# Elaborato_2021-05-28.net
KiCad netlist of a schematic drawn in EasyEDA
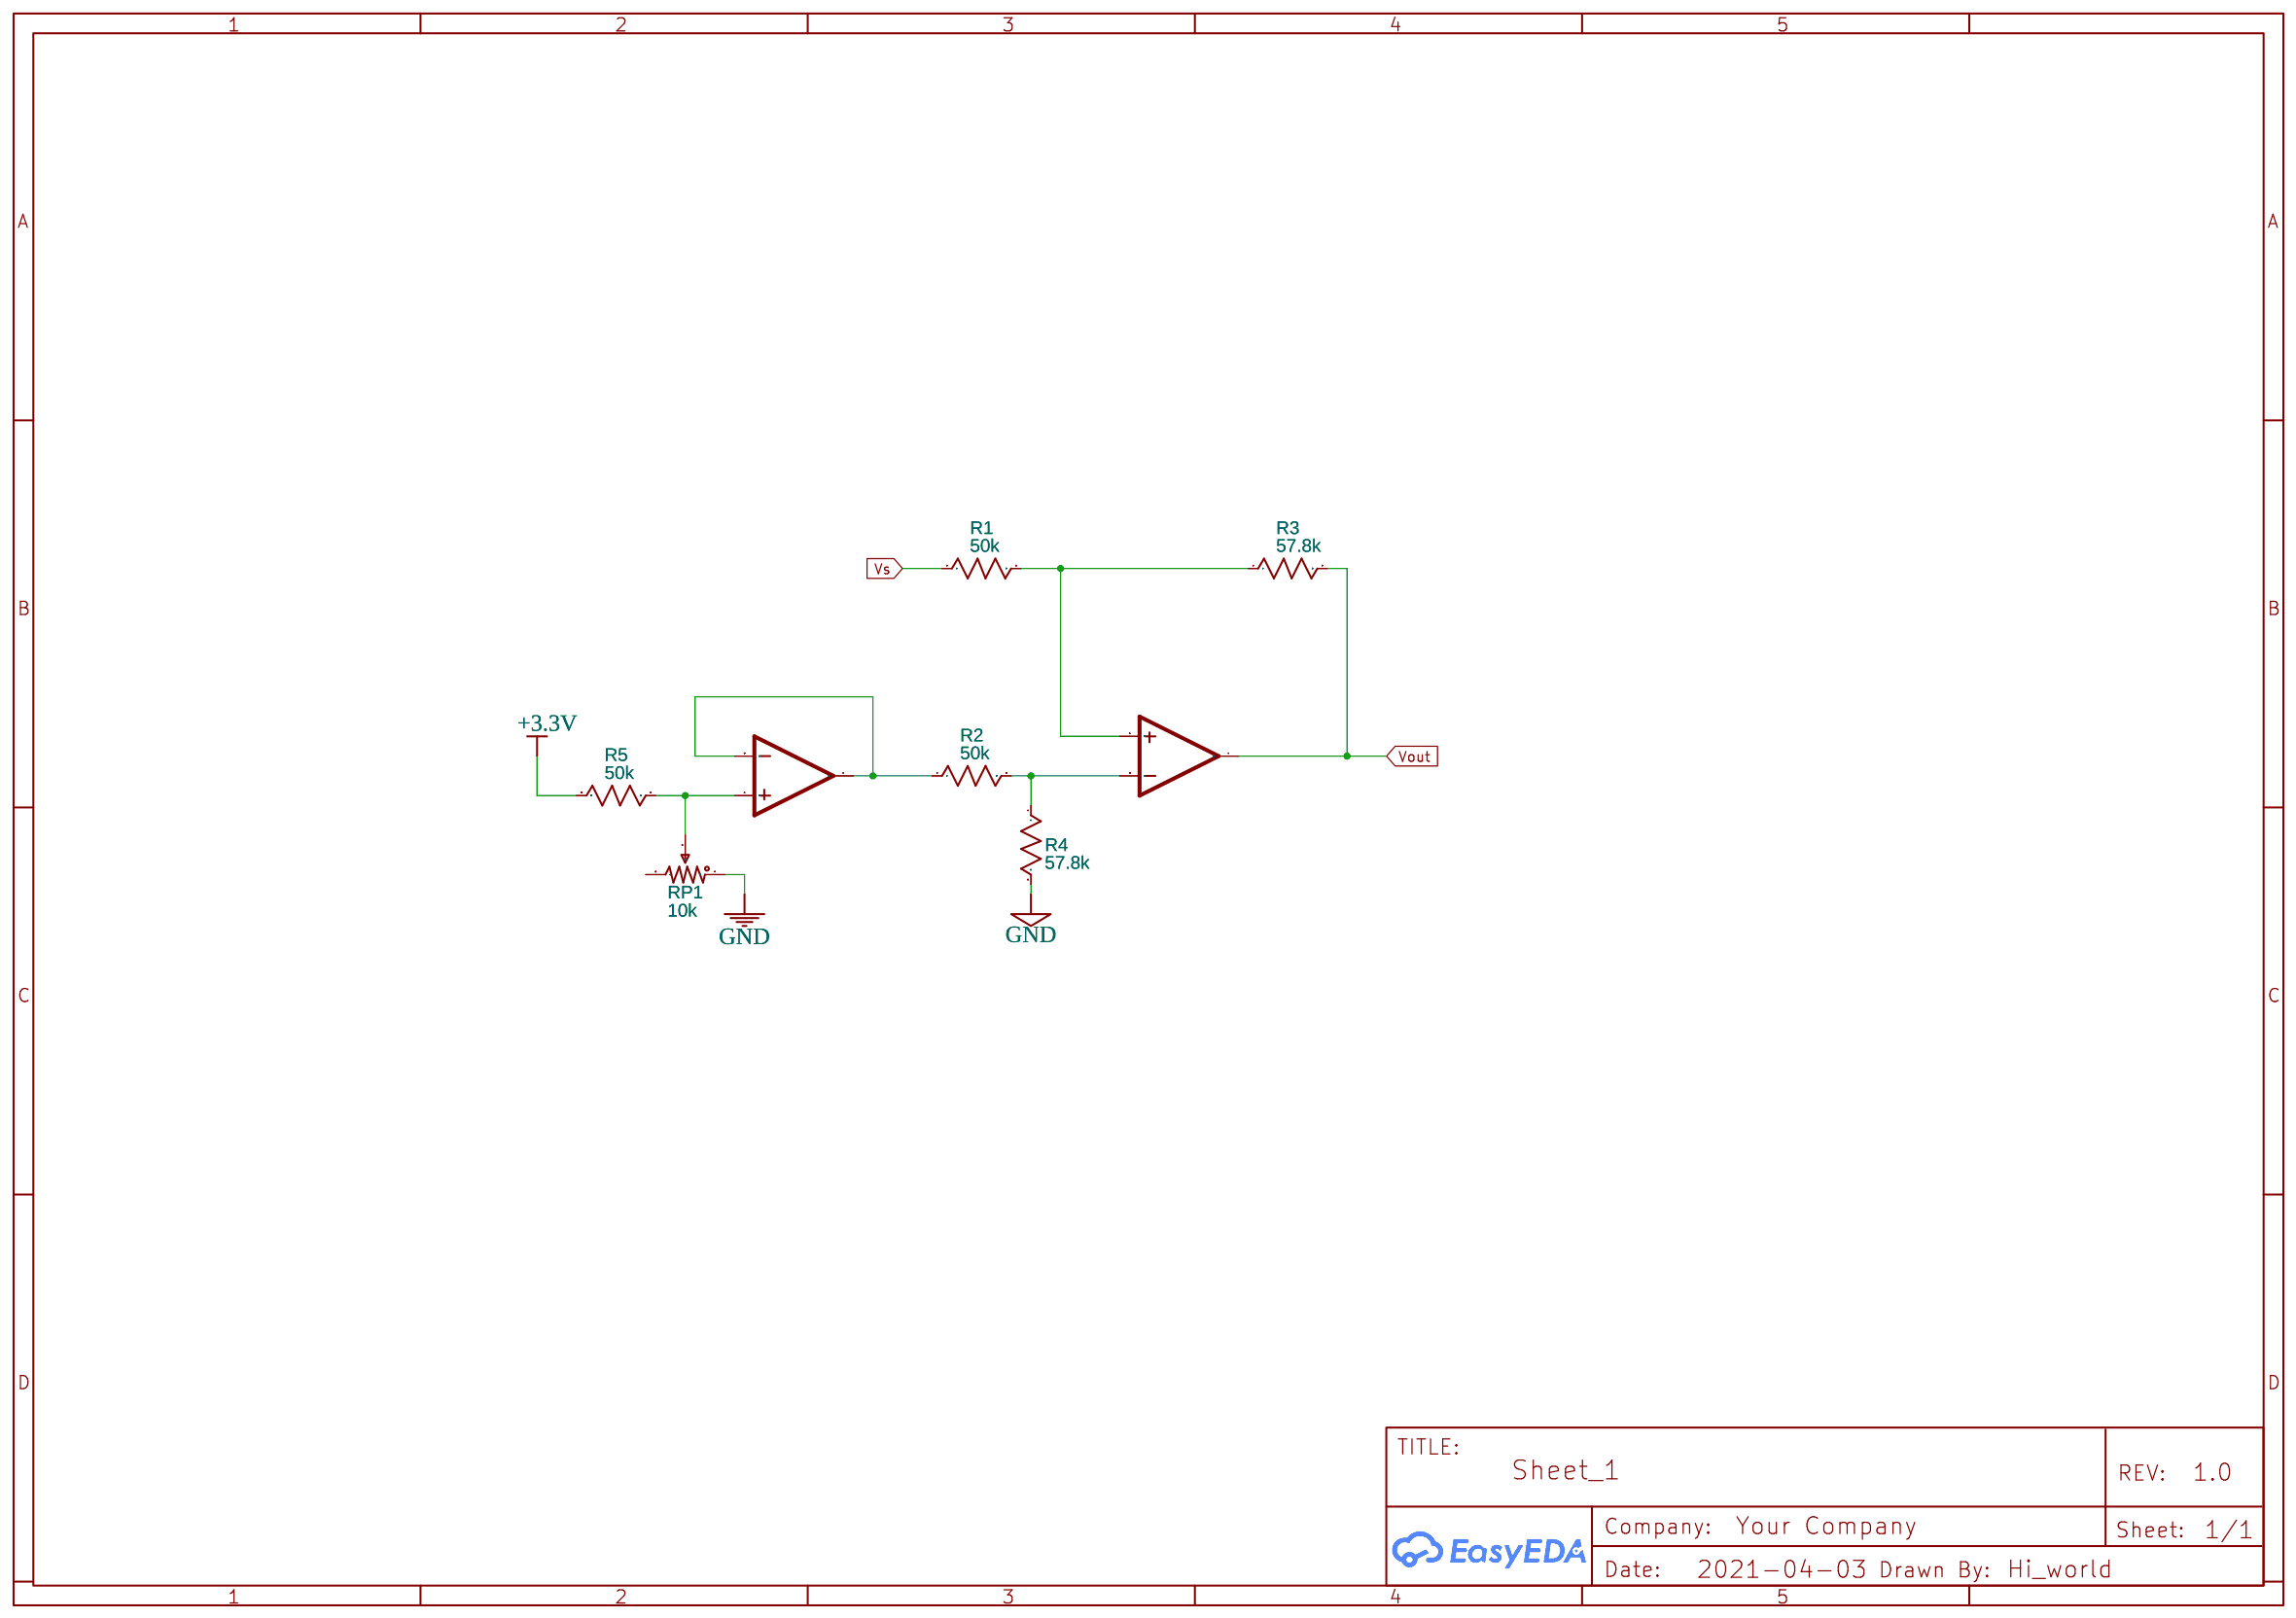
[diagram p0: Differenziale_condizionamento]
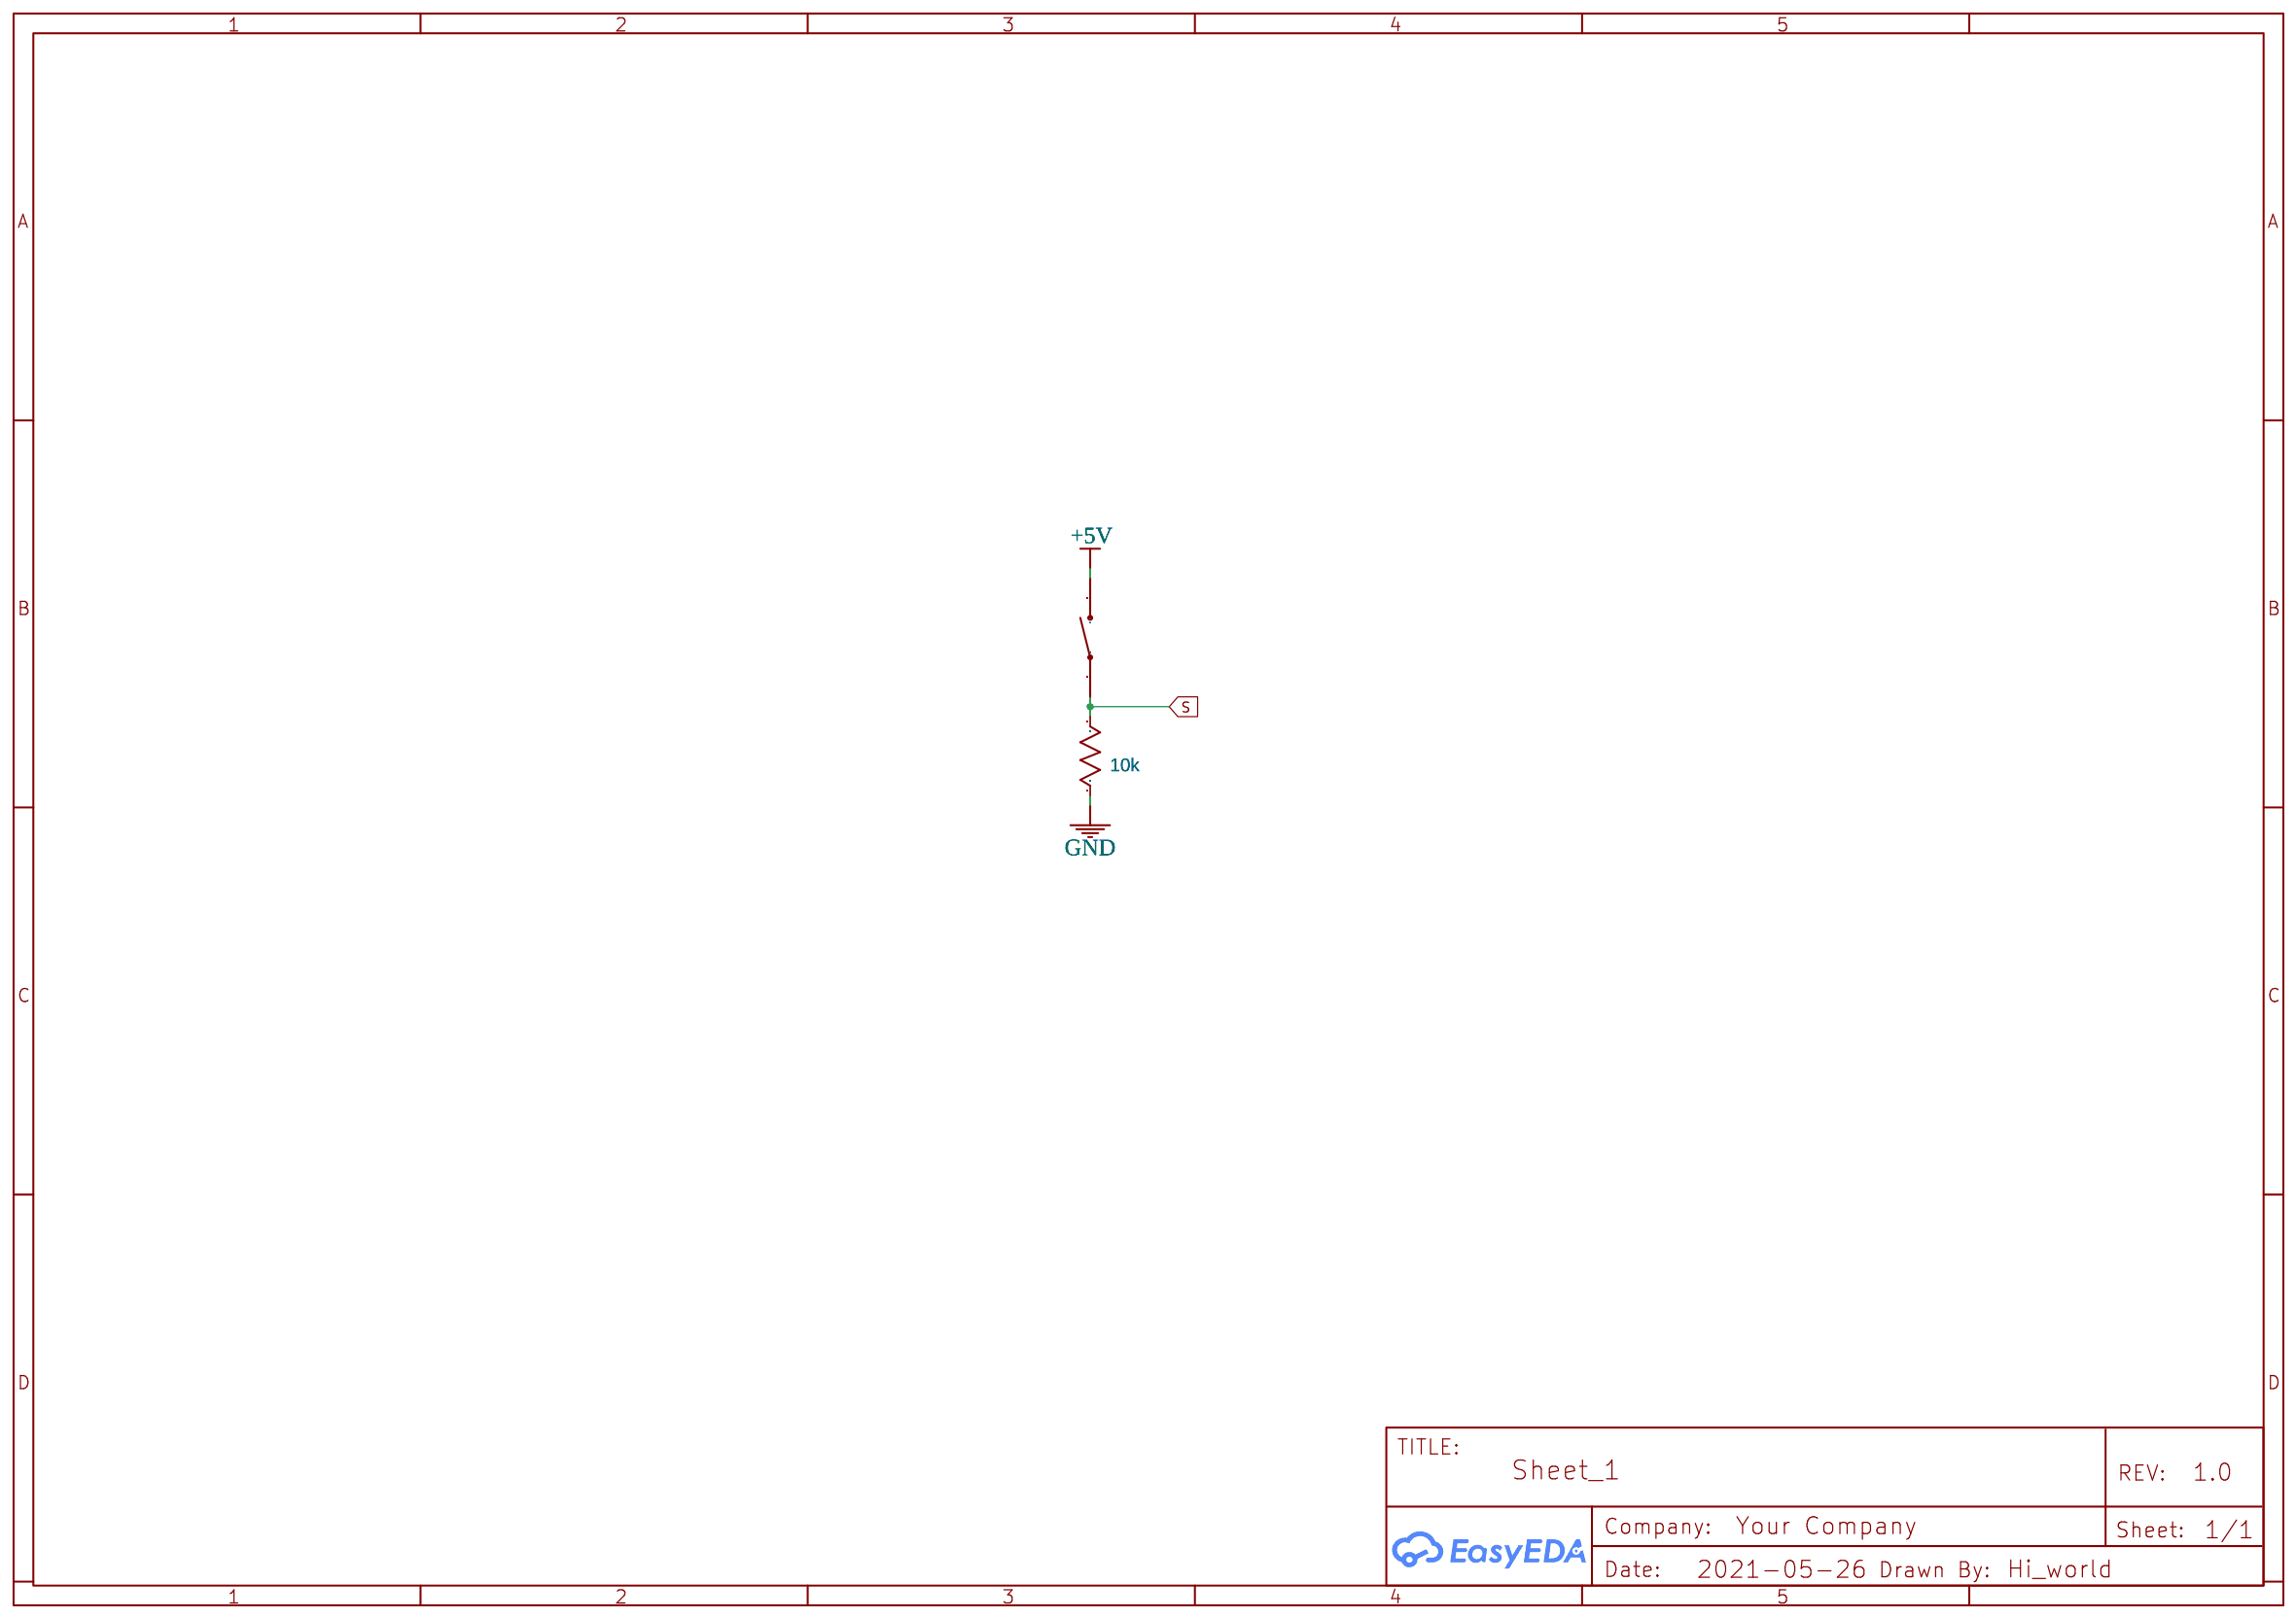
[diagram p1: Pull_down]
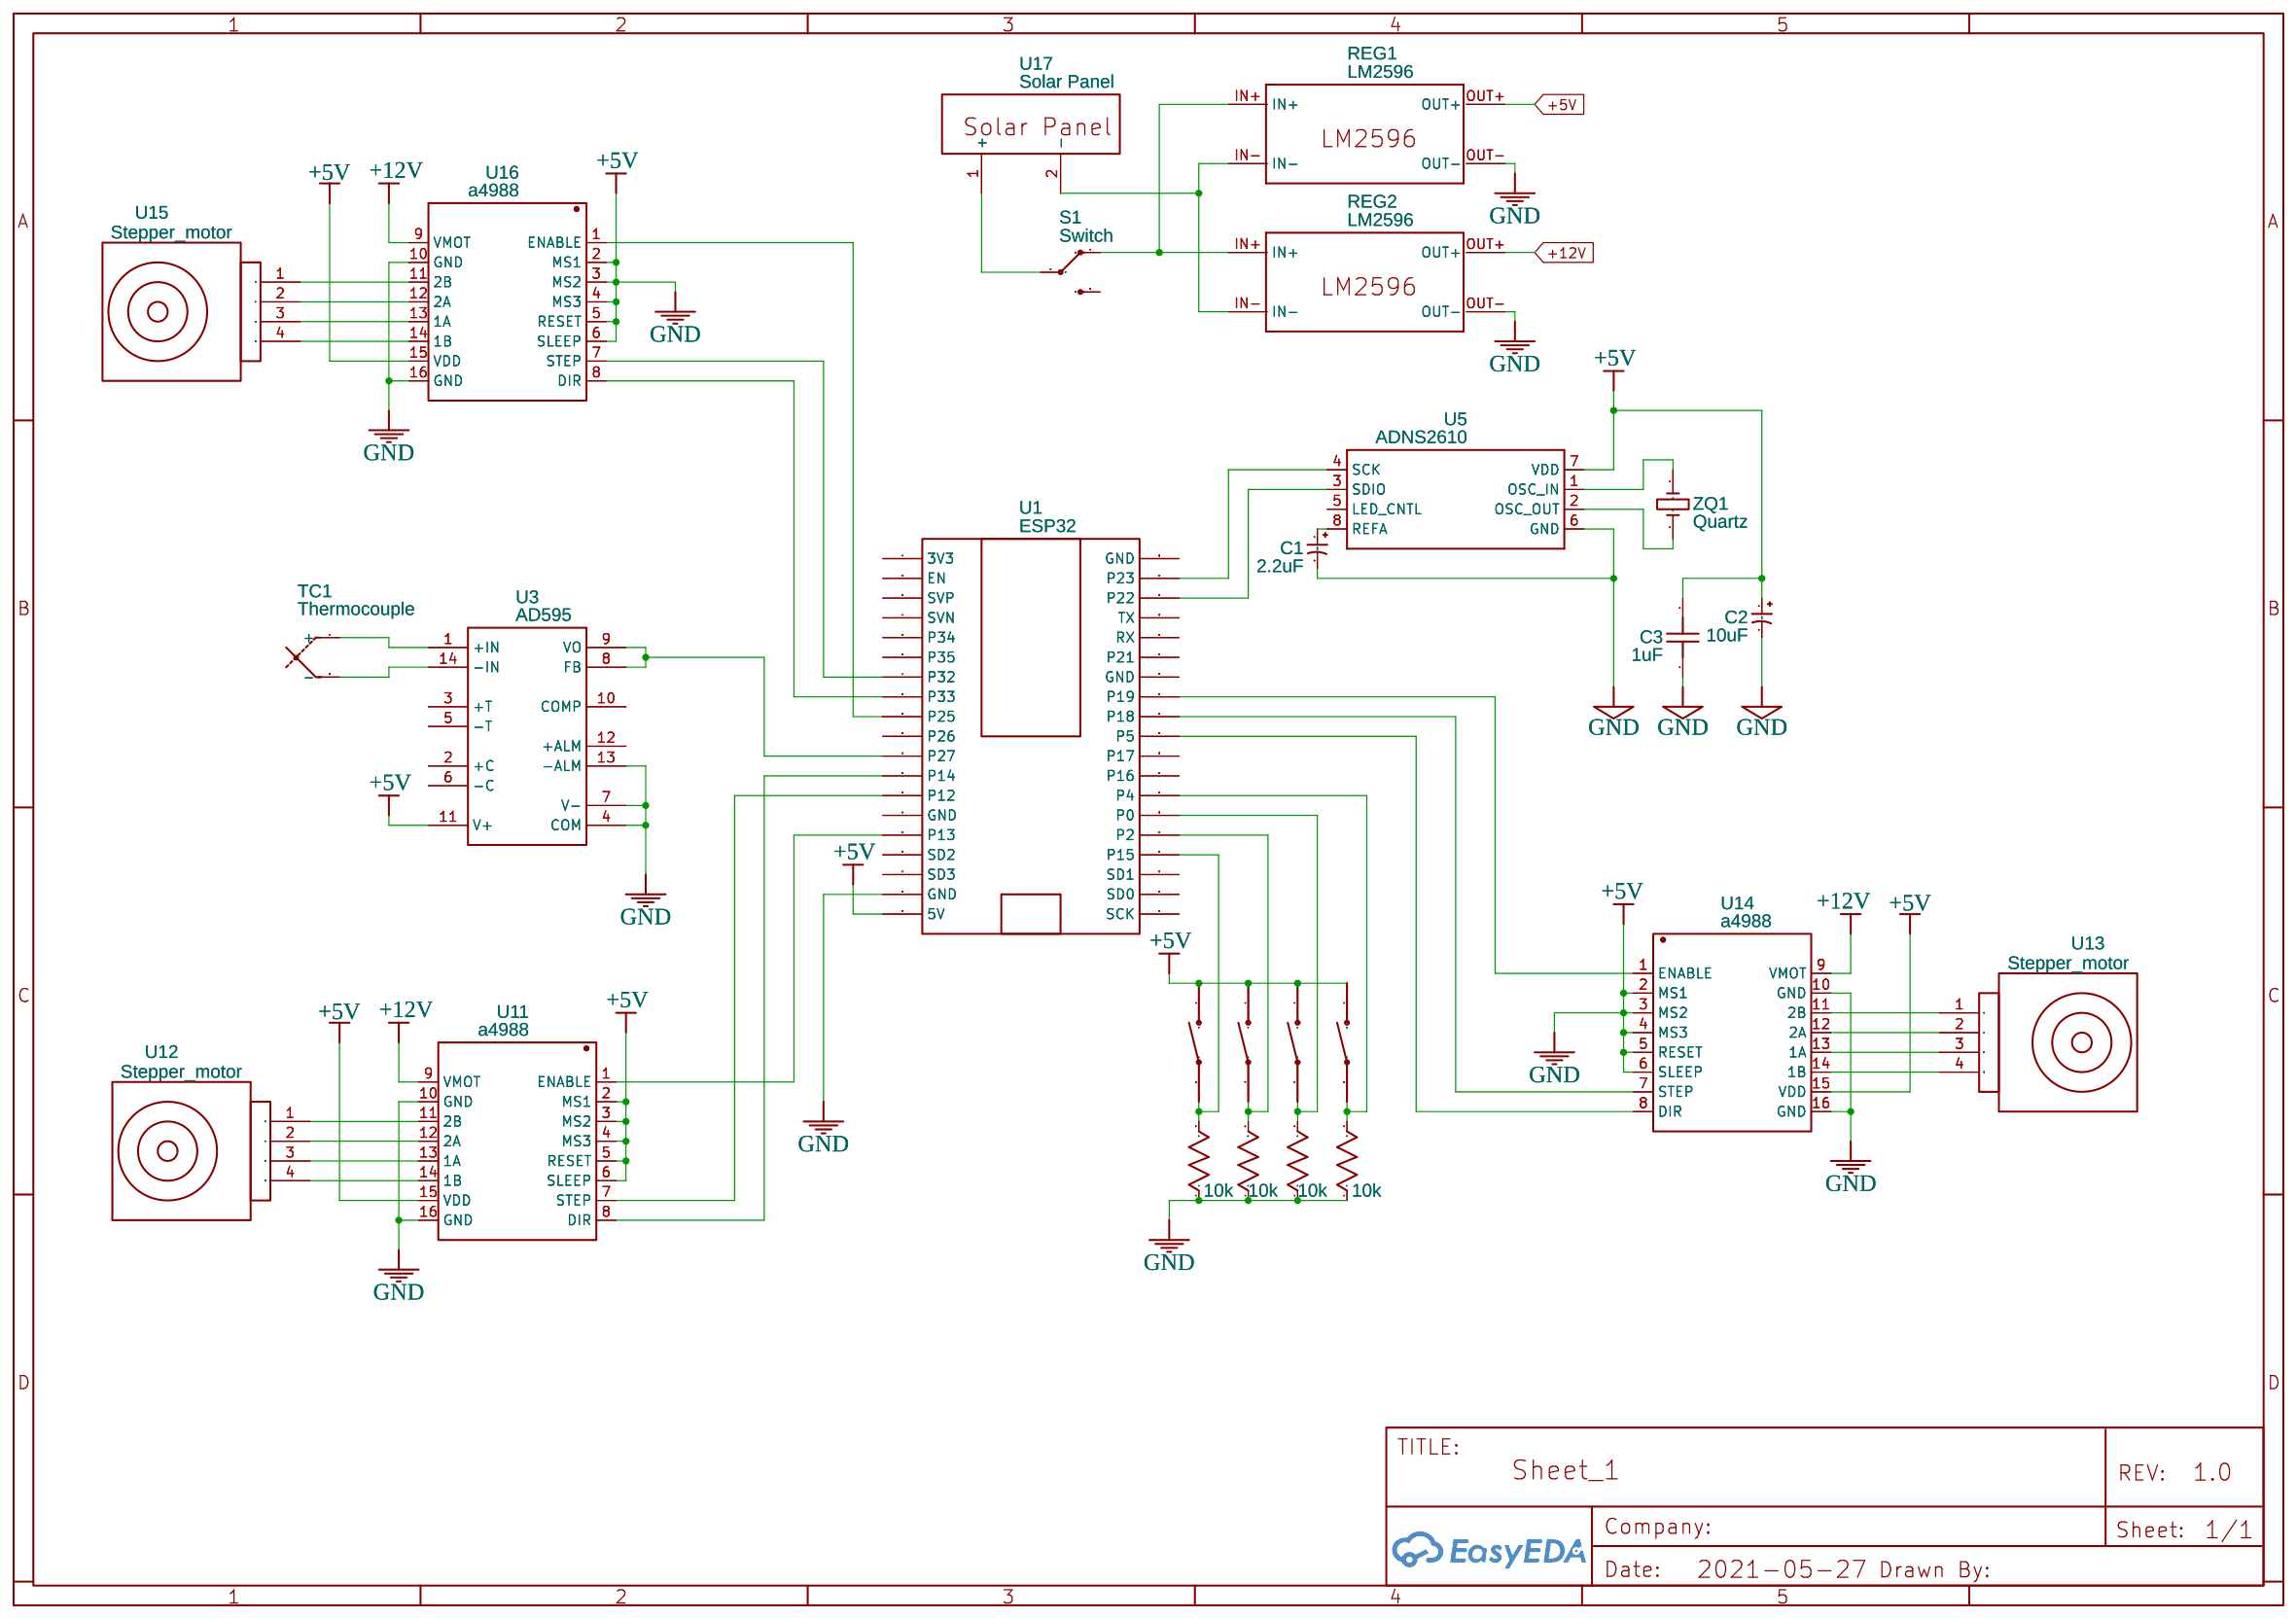
[diagram p2: Complete_schematic]

(export (version "E")
  (design (tool "Eeschema 10.0.6"))
  (components
    (comp (ref "R1") (value "50k") (libsource (lib "") (part "R_0603_US")))
    (comp (ref "R2") (value "50k") (libsource (lib "") (part "R_0603_US")))
    (comp (ref "R3") (value "57.8k") (libsource (lib "") (part "R_0603_US")))
    (comp (ref "R4") (value "57.8k") (libsource (lib "") (part "R_0603_US_1")))
    (comp (ref "R5") (value "50k") (libsource (lib "") (part "R_0603_US_2")))
    (comp (ref "RP1") (value "10k") (libsource (lib "") (part "R_3386P_US")))
    (comp (ref "U8")
      (value "Op amp")
      (fields
        (field (name "BOM_Manufacturer Part") "LMV321IDCKR")
        (field (name "BOM_Supplier Part") "310020013")
      )
      (libsource (lib "") (part "Op amp"))
    )
    (comp (ref "U9")
      (value "Op amp")
      (fields
        (field (name "BOM_Manufacturer Part") "LMV321IDCKR")
        (field (name "BOM_Supplier Part") "310020013")
      )
      (libsource (lib "") (part "Op amp_1"))
    )
    (comp (ref "R6") (value "10k") (libsource (lib "") (part "R_0603_US")))
    (comp (ref "U2")
      (value "Switch basic")
      (fields (field (name "BOM_Manufacturer Part") "Switch"))
      (libsource (lib "") (part "Switch basic"))
    )
    (comp (ref "C1") (value "2.2uF") (libsource (lib "") (part "Capacitor electrolitico 5mm_1")))
    (comp (ref "C2") (value "10uF") (libsource (lib "") (part "Capacitor electrolitico 5mm")))
    (comp (ref "C3") (value "1uF") (libsource (lib "") (part "Capacitor ceramico 5mm.PEQUEÑO")))
    (comp (ref "R7") (value "10k") (libsource (lib "") (part "R_0603_US")))
    (comp (ref "R8") (value "10k") (libsource (lib "") (part "R_0603_US")))
    (comp (ref "R9") (value "10k") (libsource (lib "") (part "R_0603_US")))
    (comp (ref "R10") (value "10k") (libsource (lib "") (part "R_0603_US")))
    (comp (ref "REG1") (value "LM2596") (libsource (lib "") (part "LM2596")))
    (comp (ref "REG2") (value "LM2596") (libsource (lib "") (part "LM2596")))
    (comp (ref "S1") (value "Switch") (libsource (lib "") (part "Switch")))
    (comp (ref "TC1") (value "Thermocouple") (libsource (lib "") (part "Thermocouple")))
    (comp (ref "U1")
      (value "ESP32")
      (fields (field (name "BOM_Manufacturer Part") "ESP-32S"))
      (libsource (lib "") (part "ESP32"))
    )
    (comp (ref "U3") (value "AD595") (libsource (lib "") (part "AD595ADZ")))
    (comp (ref "U4")
      (value "Switch basic")
      (fields (field (name "BOM_Manufacturer Part") "Switch"))
      (libsource (lib "") (part "Switch basic"))
    )
    (comp (ref "U5") (value "ADNS2610") (libsource (lib "") (part "ADNS2610")))
    (comp (ref "U6")
      (value "Switch basic")
      (fields (field (name "BOM_Manufacturer Part") "Switch"))
      (libsource (lib "") (part "Switch basic"))
    )
    (comp (ref "U7")
      (value "Switch basic")
      (fields (field (name "BOM_Manufacturer Part") "Switch"))
      (libsource (lib "") (part "Switch basic"))
    )
    (comp (ref "U10")
      (value "Switch basic")
      (fields (field (name "BOM_Manufacturer Part") "Switch"))
      (libsource (lib "") (part "Switch basic"))
    )
    (comp (ref "U11")
      (value "a4988")
      (fields
        (field (name "BOM_Manufacturer Part") "DRV8825PWPR")
        (field (name "BOM_Supplier Part") "C81582")
      )
      (libsource (lib "") (part "a4988_1"))
    )
    (comp (ref "U12")
      (value "Stepper_motor")
      (fields (field (name "BOM_Manufacturer Part") "NEMA 23 Stepper Motor"))
      (libsource (lib "") (part "Stepper_motor"))
    )
    (comp (ref "U13")
      (value "Stepper_motor")
      (fields (field (name "BOM_Manufacturer Part") "NEMA 23 Stepper Motor"))
      (libsource (lib "") (part "Stepper_motor_1"))
    )
    (comp (ref "U14")
      (value "a4988")
      (fields
        (field (name "BOM_Manufacturer Part") "DRV8825PWPR")
        (field (name "BOM_Supplier Part") "C81582")
      )
      (libsource (lib "") (part "a4988"))
    )
    (comp (ref "U15")
      (value "Stepper_motor")
      (fields (field (name "BOM_Manufacturer Part") "NEMA 23 Stepper Motor"))
      (libsource (lib "") (part "Stepper_motor"))
    )
    (comp (ref "U16")
      (value "a4988")
      (fields
        (field (name "BOM_Manufacturer Part") "DRV8825PWPR")
        (field (name "BOM_Supplier Part") "C81582")
      )
      (libsource (lib "") (part "a4988_1"))
    )
    (comp (ref "U17") (value "Solar Panel") (libsource (lib "") (part "Solar Panel")))
    (comp (ref "ZQ1")
      (value "Quartz")
      (fields (field (name "BOM_Manufacturer Part") "New SchematicLib"))
      (libsource (lib "") (part "Quartz"))
    )
  )
  (nets
    (net (code "1") (name "+3.3V") (class "Default")
      (node (ref "R5") (pin "2") (pinfunction "2_2") (pintype "unspecified"))
    )
    (net (code "2") (name "+5V") (class "Default")
      (node (ref "C1") (pin "2") (pinfunction "2_2") (pintype "unspecified"))
      (node (ref "C2") (pin "1") (pinfunction "1_1") (pintype "unspecified"))
      (node (ref "C2") (pin "2") (pinfunction "2_2") (pintype "unspecified"))
      (node (ref "C3") (pin "1") (pinfunction "1_1") (pintype "unspecified"))
      (node (ref "C3") (pin "2") (pinfunction "2_2") (pintype "unspecified"))
      (node (ref "R10") (pin "1") (pinfunction "1_1") (pintype "unspecified"))
      (node (ref "R4") (pin "2") (pinfunction "2_2") (pintype "unspecified"))
      (node (ref "R6") (pin "1") (pinfunction "1_1") (pintype "unspecified"))
      (node (ref "R7") (pin "1") (pinfunction "1_1") (pintype "unspecified"))
      (node (ref "R8") (pin "1") (pinfunction "1_1") (pintype "unspecified"))
      (node (ref "R9") (pin "1") (pinfunction "1_1") (pintype "unspecified"))
      (node (ref "REG1") (pin "OUT+") (pinfunction "OUT+_OUT+") (pintype "bidirectional"))
      (node (ref "REG1") (pin "OUT-") (pinfunction "OUT-_OUT-") (pintype "bidirectional"))
      (node (ref "REG2") (pin "OUT-") (pinfunction "OUT-_OUT-") (pintype "bidirectional"))
      (node (ref "RP1") (pin "1") (pinfunction "1_1") (pintype "unspecified"))
      (node (ref "U1") (pin "18") (pinfunction "GND_18") (pintype "unspecified"))
      (node (ref "U1") (pin "19") (pinfunction "5V_19") (pintype "unspecified"))
      (node (ref "U10") (pin "1") (pinfunction "1_1") (pintype "unspecified"))
      (node (ref "U11") (pin "10") (pinfunction "GND_10") (pintype "unspecified"))
      (node (ref "U11") (pin "15") (pinfunction "VDD_15") (pintype "unspecified"))
      (node (ref "U11") (pin "16") (pinfunction "GND_16") (pintype "unspecified"))
      (node (ref "U11") (pin "2") (pinfunction "MS1_2") (pintype "unspecified"))
      (node (ref "U11") (pin "3") (pinfunction "MS2_3") (pintype "unspecified"))
      (node (ref "U11") (pin "4") (pinfunction "MS3_4") (pintype "unspecified"))
      (node (ref "U11") (pin "5") (pinfunction "RESET_5") (pintype "unspecified"))
      (node (ref "U11") (pin "6") (pinfunction "SLEEP_6") (pintype "unspecified"))
      (node (ref "U14") (pin "10") (pinfunction "GND_10") (pintype "unspecified"))
      (node (ref "U14") (pin "15") (pinfunction "VDD_15") (pintype "unspecified"))
      (node (ref "U14") (pin "16") (pinfunction "GND_16") (pintype "unspecified"))
      (node (ref "U14") (pin "2") (pinfunction "MS1_2") (pintype "unspecified"))
      (node (ref "U14") (pin "3") (pinfunction "MS2_3") (pintype "unspecified"))
      (node (ref "U14") (pin "4") (pinfunction "MS3_4") (pintype "unspecified"))
      (node (ref "U14") (pin "5") (pinfunction "RESET_5") (pintype "unspecified"))
      (node (ref "U14") (pin "6") (pinfunction "SLEEP_6") (pintype "unspecified"))
      (node (ref "U16") (pin "10") (pinfunction "GND_10") (pintype "unspecified"))
      (node (ref "U16") (pin "15") (pinfunction "VDD_15") (pintype "unspecified"))
      (node (ref "U16") (pin "16") (pinfunction "GND_16") (pintype "unspecified"))
      (node (ref "U16") (pin "2") (pinfunction "MS1_2") (pintype "unspecified"))
      (node (ref "U16") (pin "3") (pinfunction "MS2_3") (pintype "unspecified"))
      (node (ref "U16") (pin "4") (pinfunction "MS3_4") (pintype "unspecified"))
      (node (ref "U16") (pin "5") (pinfunction "RESET_5") (pintype "unspecified"))
      (node (ref "U16") (pin "6") (pinfunction "SLEEP_6") (pintype "unspecified"))
      (node (ref "U2") (pin "1") (pinfunction "1_1") (pintype "unspecified"))
      (node (ref "U3") (pin "11") (pinfunction "V+_11") (pintype "passive"))
      (node (ref "U3") (pin "13") (pinfunction "-ALM_13") (pintype "unspecified"))
      (node (ref "U3") (pin "4") (pinfunction "COM_4") (pintype "passive"))
      (node (ref "U3") (pin "7") (pinfunction "V-_7") (pintype "passive"))
      (node (ref "U4") (pin "1") (pinfunction "1_1") (pintype "unspecified"))
      (node (ref "U5") (pin "6") (pinfunction "GND_6") (pintype "unspecified"))
      (node (ref "U5") (pin "7") (pinfunction "VDD_7") (pintype "unspecified"))
      (node (ref "U6") (pin "1") (pinfunction "1_1") (pintype "unspecified"))
      (node (ref "U7") (pin "1") (pinfunction "1_1") (pintype "unspecified"))
    )
    (net (code "3") (name "+12V") (class "Default")
      (node (ref "REG2") (pin "OUT+") (pinfunction "OUT+_OUT+") (pintype "bidirectional"))
      (node (ref "U11") (pin "9") (pinfunction "VMOT_9") (pintype "unspecified"))
      (node (ref "U14") (pin "9") (pinfunction "VMOT_9") (pintype "unspecified"))
      (node (ref "U16") (pin "9") (pinfunction "VMOT_9") (pintype "unspecified"))
    )
    (net (code "4") (name "Net-(S1-O)") (class "Default")
      (node (ref "REG1") (pin "IN+") (pinfunction "IN+_IN+") (pintype "bidirectional"))
      (node (ref "REG2") (pin "IN+") (pinfunction "IN+_IN+") (pintype "bidirectional"))
      (node (ref "S1") (pin "1") (pinfunction "O_1") (pintype "unspecified"))
    )
    (net (code "5") (name "Net-(S1-P)") (class "Default")
      (node (ref "S1") (pin "2") (pinfunction "P_2") (pintype "unspecified"))
      (node (ref "U17") (pin "1") (pinfunction "+_1") (pintype "unspecified"))
    )
    (net (code "6") (name "Net-(TC1-+)") (class "Default")
      (node (ref "TC1") (pin "1") (pinfunction "+_1") (pintype "unspecified"))
      (node (ref "U3") (pin "1") (pinfunction "+IN_1") (pintype "unspecified"))
    )
    (net (code "7") (name "Net-(TC1--)") (class "Default")
      (node (ref "TC1") (pin "2") (pinfunction "-_2") (pintype "unspecified"))
      (node (ref "U3") (pin "14") (pinfunction "-IN_14") (pintype "unspecified"))
    )
    (net (code "8") (name "Net-(U1-P0)") (class "Default")
      (node (ref "R9") (pin "2") (pinfunction "2_2") (pintype "unspecified"))
      (node (ref "U1") (pin "25") (pinfunction "P0_25") (pintype "unspecified"))
      (node (ref "U7") (pin "2") (pinfunction "2_2") (pintype "unspecified"))
    )
    (net (code "9") (name "Net-(U1-P2)") (class "Default")
      (node (ref "R8") (pin "2") (pinfunction "2_2") (pintype "unspecified"))
      (node (ref "U1") (pin "24") (pinfunction "P2_24") (pintype "unspecified"))
      (node (ref "U6") (pin "2") (pinfunction "2_2") (pintype "unspecified"))
    )
    (net (code "10") (name "Net-(U1-P4)") (class "Default")
      (node (ref "R10") (pin "2") (pinfunction "2_2") (pintype "unspecified"))
      (node (ref "U1") (pin "26") (pinfunction "P4_26") (pintype "unspecified"))
      (node (ref "U10") (pin "2") (pinfunction "2_2") (pintype "unspecified"))
    )
    (net (code "11") (name "Net-(U1-P5)") (class "Default")
      (node (ref "U1") (pin "29") (pinfunction "P5_29") (pintype "unspecified"))
      (node (ref "U14") (pin "8") (pinfunction "DIR_8") (pintype "unspecified"))
    )
    (net (code "12") (name "Net-(U1-P12)") (class "Default")
      (node (ref "U1") (pin "13") (pinfunction "P12_13") (pintype "unspecified"))
      (node (ref "U11") (pin "7") (pinfunction "STEP_7") (pintype "unspecified"))
    )
    (net (code "13") (name "Net-(U1-P13)") (class "Default")
      (node (ref "U1") (pin "15") (pinfunction "P13_15") (pintype "unspecified"))
      (node (ref "U11") (pin "1") (pinfunction "ENABLE_1") (pintype "unspecified"))
    )
    (net (code "14") (name "Net-(U1-P14)") (class "Default")
      (node (ref "U1") (pin "12") (pinfunction "P14_12") (pintype "unspecified"))
      (node (ref "U11") (pin "8") (pinfunction "DIR_8") (pintype "unspecified"))
    )
    (net (code "15") (name "Net-(U1-P15)") (class "Default")
      (node (ref "R7") (pin "2") (pinfunction "2_2") (pintype "unspecified"))
      (node (ref "U1") (pin "23") (pinfunction "P15_23") (pintype "unspecified"))
      (node (ref "U4") (pin "2") (pinfunction "2_2") (pintype "unspecified"))
    )
    (net (code "16") (name "Net-(U1-P18)") (class "Default")
      (node (ref "U1") (pin "30") (pinfunction "P18_30") (pintype "unspecified"))
      (node (ref "U14") (pin "7") (pinfunction "STEP_7") (pintype "unspecified"))
    )
    (net (code "17") (name "Net-(U1-P19)") (class "Default")
      (node (ref "U1") (pin "31") (pinfunction "P19_31") (pintype "unspecified"))
      (node (ref "U14") (pin "1") (pinfunction "ENABLE_1") (pintype "unspecified"))
    )
    (net (code "18") (name "Net-(U1-P22)") (class "Default")
      (node (ref "U1") (pin "36") (pinfunction "P22_36") (pintype "unspecified"))
      (node (ref "U5") (pin "3") (pinfunction "SDIO_3") (pintype "unspecified"))
    )
    (net (code "19") (name "Net-(U1-P23)") (class "Default")
      (node (ref "U1") (pin "37") (pinfunction "P23_37") (pintype "unspecified"))
      (node (ref "U5") (pin "4") (pinfunction "SCK_4") (pintype "unspecified"))
    )
    (net (code "20") (name "Net-(U1-P25)") (class "Default")
      (node (ref "U1") (pin "9") (pinfunction "P25_9") (pintype "unspecified"))
      (node (ref "U16") (pin "1") (pinfunction "ENABLE_1") (pintype "unspecified"))
    )
    (net (code "21") (name "Net-(U1-P27)") (class "Default")
      (node (ref "U1") (pin "11") (pinfunction "P27_11") (pintype "unspecified"))
      (node (ref "U3") (pin "8") (pinfunction "FB_8") (pintype "unspecified"))
      (node (ref "U3") (pin "9") (pinfunction "VO_9") (pintype "output"))
    )
    (net (code "22") (name "Net-(U1-P32)") (class "Default")
      (node (ref "U1") (pin "7") (pinfunction "P32_7") (pintype "unspecified"))
      (node (ref "U16") (pin "7") (pinfunction "STEP_7") (pintype "unspecified"))
    )
    (net (code "23") (name "Net-(U1-P33)") (class "Default")
      (node (ref "U1") (pin "8") (pinfunction "P33_8") (pintype "unspecified"))
      (node (ref "U16") (pin "8") (pinfunction "DIR_8") (pintype "unspecified"))
    )
    (net (code "24") (name "Net-(U5-OSC_IN)") (class "Default")
      (node (ref "U5") (pin "1") (pinfunction "OSC_IN_1") (pintype "unspecified"))
      (node (ref "ZQ1") (pin "2") (pinfunction "2_2") (pintype "unspecified"))
    )
    (net (code "25") (name "Net-(U5-OSC_OUT)") (class "Default")
      (node (ref "U5") (pin "2") (pinfunction "OSC_OUT_2") (pintype "unspecified"))
      (node (ref "ZQ1") (pin "1") (pinfunction "1_1") (pintype "unspecified"))
    )
    (net (code "26") (name "Net-(U5-REFA)") (class "Default")
      (node (ref "C1") (pin "1") (pinfunction "1_1") (pintype "unspecified"))
      (node (ref "U5") (pin "8") (pinfunction "REFA_8") (pintype "unspecified"))
    )
    (net (code "27") (name "Net-(U8-IN+)") (class "Default")
      (node (ref "R5") (pin "1") (pinfunction "1_1") (pintype "unspecified"))
      (node (ref "RP1") (pin "2") (pinfunction "2_2") (pintype "unspecified"))
      (node (ref "U8") (pin "1") (pinfunction "IN+_1") (pintype "input"))
    )
    (net (code "28") (name "Net-(U8-IN-)") (class "Default")
      (node (ref "R2") (pin "1") (pinfunction "1_1") (pintype "unspecified"))
      (node (ref "U8") (pin "3") (pinfunction "IN-_3") (pintype "input"))
      (node (ref "U8") (pin "4") (pinfunction "OUT_4") (pintype "output"))
    )
    (net (code "29") (name "Net-(U9-IN+)") (class "Default")
      (node (ref "R1") (pin "2") (pinfunction "2_2") (pintype "unspecified"))
      (node (ref "R3") (pin "1") (pinfunction "1_1") (pintype "unspecified"))
      (node (ref "U9") (pin "1") (pinfunction "IN+_1") (pintype "input"))
    )
    (net (code "30") (name "Net-(U9-IN-)") (class "Default")
      (node (ref "R2") (pin "2") (pinfunction "2_2") (pintype "unspecified"))
      (node (ref "R4") (pin "1") (pinfunction "1_1") (pintype "unspecified"))
      (node (ref "U9") (pin "3") (pinfunction "IN-_3") (pintype "input"))
    )
    (net (code "31") (name "Net-(U11-1A)") (class "Default")
      (node (ref "U11") (pin "13") (pinfunction "1A_13") (pintype "unspecified"))
      (node (ref "U12") (pin "3") (pinfunction "B+_3") (pintype "unspecified"))
    )
    (net (code "32") (name "Net-(U11-1B)") (class "Default")
      (node (ref "U11") (pin "14") (pinfunction "1B_14") (pintype "unspecified"))
      (node (ref "U12") (pin "4") (pinfunction "B-_4") (pintype "unspecified"))
    )
    (net (code "33") (name "Net-(U11-2A)") (class "Default")
      (node (ref "U11") (pin "12") (pinfunction "2A_12") (pintype "unspecified"))
      (node (ref "U12") (pin "2") (pinfunction "A-_2") (pintype "unspecified"))
    )
    (net (code "34") (name "Net-(U11-2B)") (class "Default")
      (node (ref "U11") (pin "11") (pinfunction "2B_11") (pintype "unspecified"))
      (node (ref "U12") (pin "1") (pinfunction "A+_1") (pintype "unspecified"))
    )
    (net (code "35") (name "Net-(U13-A+)") (class "Default")
      (node (ref "U13") (pin "1") (pinfunction "A+_1") (pintype "unspecified"))
      (node (ref "U14") (pin "11") (pinfunction "2B_11") (pintype "unspecified"))
    )
    (net (code "36") (name "Net-(U13-A-)") (class "Default")
      (node (ref "U13") (pin "2") (pinfunction "A-_2") (pintype "unspecified"))
      (node (ref "U14") (pin "12") (pinfunction "2A_12") (pintype "unspecified"))
    )
    (net (code "37") (name "Net-(U13-B+)") (class "Default")
      (node (ref "U13") (pin "3") (pinfunction "B+_3") (pintype "unspecified"))
      (node (ref "U14") (pin "13") (pinfunction "1A_13") (pintype "unspecified"))
    )
    (net (code "38") (name "Net-(U13-B-)") (class "Default")
      (node (ref "U13") (pin "4") (pinfunction "B-_4") (pintype "unspecified"))
      (node (ref "U14") (pin "14") (pinfunction "1B_14") (pintype "unspecified"))
    )
    (net (code "39") (name "Net-(U15-A+)") (class "Default")
      (node (ref "U15") (pin "1") (pinfunction "A+_1") (pintype "unspecified"))
      (node (ref "U16") (pin "11") (pinfunction "2B_11") (pintype "unspecified"))
    )
    (net (code "40") (name "Net-(U15-A-)") (class "Default")
      (node (ref "U15") (pin "2") (pinfunction "A-_2") (pintype "unspecified"))
      (node (ref "U16") (pin "12") (pinfunction "2A_12") (pintype "unspecified"))
    )
    (net (code "41") (name "Net-(U15-B+)") (class "Default")
      (node (ref "U15") (pin "3") (pinfunction "B+_3") (pintype "unspecified"))
      (node (ref "U16") (pin "13") (pinfunction "1A_13") (pintype "unspecified"))
    )
    (net (code "42") (name "Net-(U15-B-)") (class "Default")
      (node (ref "U15") (pin "4") (pinfunction "B-_4") (pintype "unspecified"))
      (node (ref "U16") (pin "14") (pinfunction "1B_14") (pintype "unspecified"))
    )
    (net (code "43") (name "Net-(U17--)") (class "Default")
      (node (ref "REG1") (pin "IN-") (pinfunction "IN-_IN-") (pintype "bidirectional"))
      (node (ref "REG2") (pin "IN-") (pinfunction "IN-_IN-") (pintype "bidirectional"))
      (node (ref "U17") (pin "2") (pinfunction "-_2") (pintype "unspecified"))
    )
    (net (code "44") (name "S") (class "Default")
      (node (ref "R6") (pin "2") (pinfunction "2_2") (pintype "unspecified"))
      (node (ref "U2") (pin "2") (pinfunction "2_2") (pintype "unspecified"))
    )
    (net (code "45") (name "Vout") (class "Default")
      (node (ref "R3") (pin "2") (pinfunction "2_2") (pintype "unspecified"))
      (node (ref "U9") (pin "4") (pinfunction "OUT_4") (pintype "output"))
    )
    (net (code "46") (name "Vs") (class "Default")
      (node (ref "R1") (pin "1") (pinfunction "1_1") (pintype "unspecified"))
    )
    (net (code "47") (name "unconnected-(RP1-Pad3)") (class "Default")
      (node (ref "RP1") (pin "3") (pinfunction "3_3") (pintype "unspecified"))
    )
    (net (code "48") (name "unconnected-(S1-S-Pad3)") (class "Default")
      (node (ref "S1") (pin "3") (pinfunction "S_3") (pintype "unspecified"))
    )
    (net (code "49") (name "unconnected-(U1-3V3-Pad1)") (class "Default")
      (node (ref "U1") (pin "1") (pinfunction "3V3_1") (pintype "unspecified"))
    )
    (net (code "50") (name "unconnected-(U1-EN-Pad2)") (class "Default")
      (node (ref "U1") (pin "2") (pinfunction "EN_2") (pintype "unspecified"))
    )
    (net (code "51") (name "unconnected-(U1-GND-Pad14)") (class "Default")
      (node (ref "U1") (pin "14") (pinfunction "GND_14") (pintype "unspecified"))
    )
    (net (code "52") (name "unconnected-(U1-GND-Pad32)") (class "Default")
      (node (ref "U1") (pin "32") (pinfunction "GND_32") (pintype "unspecified"))
    )
    (net (code "53") (name "unconnected-(U1-GND-Pad38)") (class "Default")
      (node (ref "U1") (pin "38") (pinfunction "GND_38") (pintype "unspecified"))
    )
    (net (code "54") (name "unconnected-(U1-P16-Pad27)") (class "Default")
      (node (ref "U1") (pin "27") (pinfunction "P16_27") (pintype "unspecified"))
    )
    (net (code "55") (name "unconnected-(U1-P17-Pad28)") (class "Default")
      (node (ref "U1") (pin "28") (pinfunction "P17_28") (pintype "unspecified"))
    )
    (net (code "56") (name "unconnected-(U1-P21-Pad33)") (class "Default")
      (node (ref "U1") (pin "33") (pinfunction "P21_33") (pintype "unspecified"))
    )
    (net (code "57") (name "unconnected-(U1-P26-Pad10)") (class "Default")
      (node (ref "U1") (pin "10") (pinfunction "P26_10") (pintype "unspecified"))
    )
    (net (code "58") (name "unconnected-(U1-P34-Pad5)") (class "Default")
      (node (ref "U1") (pin "5") (pinfunction "P34_5") (pintype "unspecified"))
    )
    (net (code "59") (name "unconnected-(U1-P35-Pad6)") (class "Default")
      (node (ref "U1") (pin "6") (pinfunction "P35_6") (pintype "unspecified"))
    )
    (net (code "60") (name "unconnected-(U1-RX-Pad34)") (class "Default")
      (node (ref "U1") (pin "34") (pinfunction "RX_34") (pintype "unspecified"))
    )
    (net (code "61") (name "unconnected-(U1-SCK-Pad20)") (class "Default")
      (node (ref "U1") (pin "20") (pinfunction "SCK_20") (pintype "unspecified"))
    )
    (net (code "62") (name "unconnected-(U1-SD0-Pad21)") (class "Default")
      (node (ref "U1") (pin "21") (pinfunction "SD0_21") (pintype "unspecified"))
    )
    (net (code "63") (name "unconnected-(U1-SD1-Pad22)") (class "Default")
      (node (ref "U1") (pin "22") (pinfunction "SD1_22") (pintype "unspecified"))
    )
    (net (code "64") (name "unconnected-(U1-SD2-Pad16)") (class "Default")
      (node (ref "U1") (pin "16") (pinfunction "SD2_16") (pintype "unspecified"))
    )
    (net (code "65") (name "unconnected-(U1-SD3-Pad17)") (class "Default")
      (node (ref "U1") (pin "17") (pinfunction "SD3_17") (pintype "unspecified"))
    )
    (net (code "66") (name "unconnected-(U1-SVN-Pad4)") (class "Default")
      (node (ref "U1") (pin "4") (pinfunction "SVN_4") (pintype "unspecified"))
    )
    (net (code "67") (name "unconnected-(U1-SVP-Pad3)") (class "Default")
      (node (ref "U1") (pin "3") (pinfunction "SVP_3") (pintype "unspecified"))
    )
    (net (code "68") (name "unconnected-(U1-TX-Pad35)") (class "Default")
      (node (ref "U1") (pin "35") (pinfunction "TX_35") (pintype "unspecified"))
    )
    (net (code "69") (name "unconnected-(U3-+ALM-Pad12)") (class "Default")
      (node (ref "U3") (pin "12") (pinfunction "+ALM_12") (pintype "unspecified"))
    )
    (net (code "70") (name "unconnected-(U3-+C-Pad2)") (class "Default")
      (node (ref "U3") (pin "2") (pinfunction "+C_2") (pintype "unspecified"))
    )
    (net (code "71") (name "unconnected-(U3-+T-Pad3)") (class "Default")
      (node (ref "U3") (pin "3") (pinfunction "+T_3") (pintype "unspecified"))
    )
    (net (code "72") (name "unconnected-(U3--C-Pad6)") (class "Default")
      (node (ref "U3") (pin "6") (pinfunction "-C_6") (pintype "unspecified"))
    )
    (net (code "73") (name "unconnected-(U3--T-Pad5)") (class "Default")
      (node (ref "U3") (pin "5") (pinfunction "-T_5") (pintype "unspecified"))
    )
    (net (code "74") (name "unconnected-(U3-COMP-Pad10)") (class "Default")
      (node (ref "U3") (pin "10") (pinfunction "COMP_10") (pintype "output"))
    )
    (net (code "75") (name "unconnected-(U5-LED_CNTL-Pad5)") (class "Default")
      (node (ref "U5") (pin "5") (pinfunction "LED_CNTL_5") (pintype "unspecified"))
    )
  )
)
